# door_board.net
KiCad netlist of a schematic drawn in EAGLE
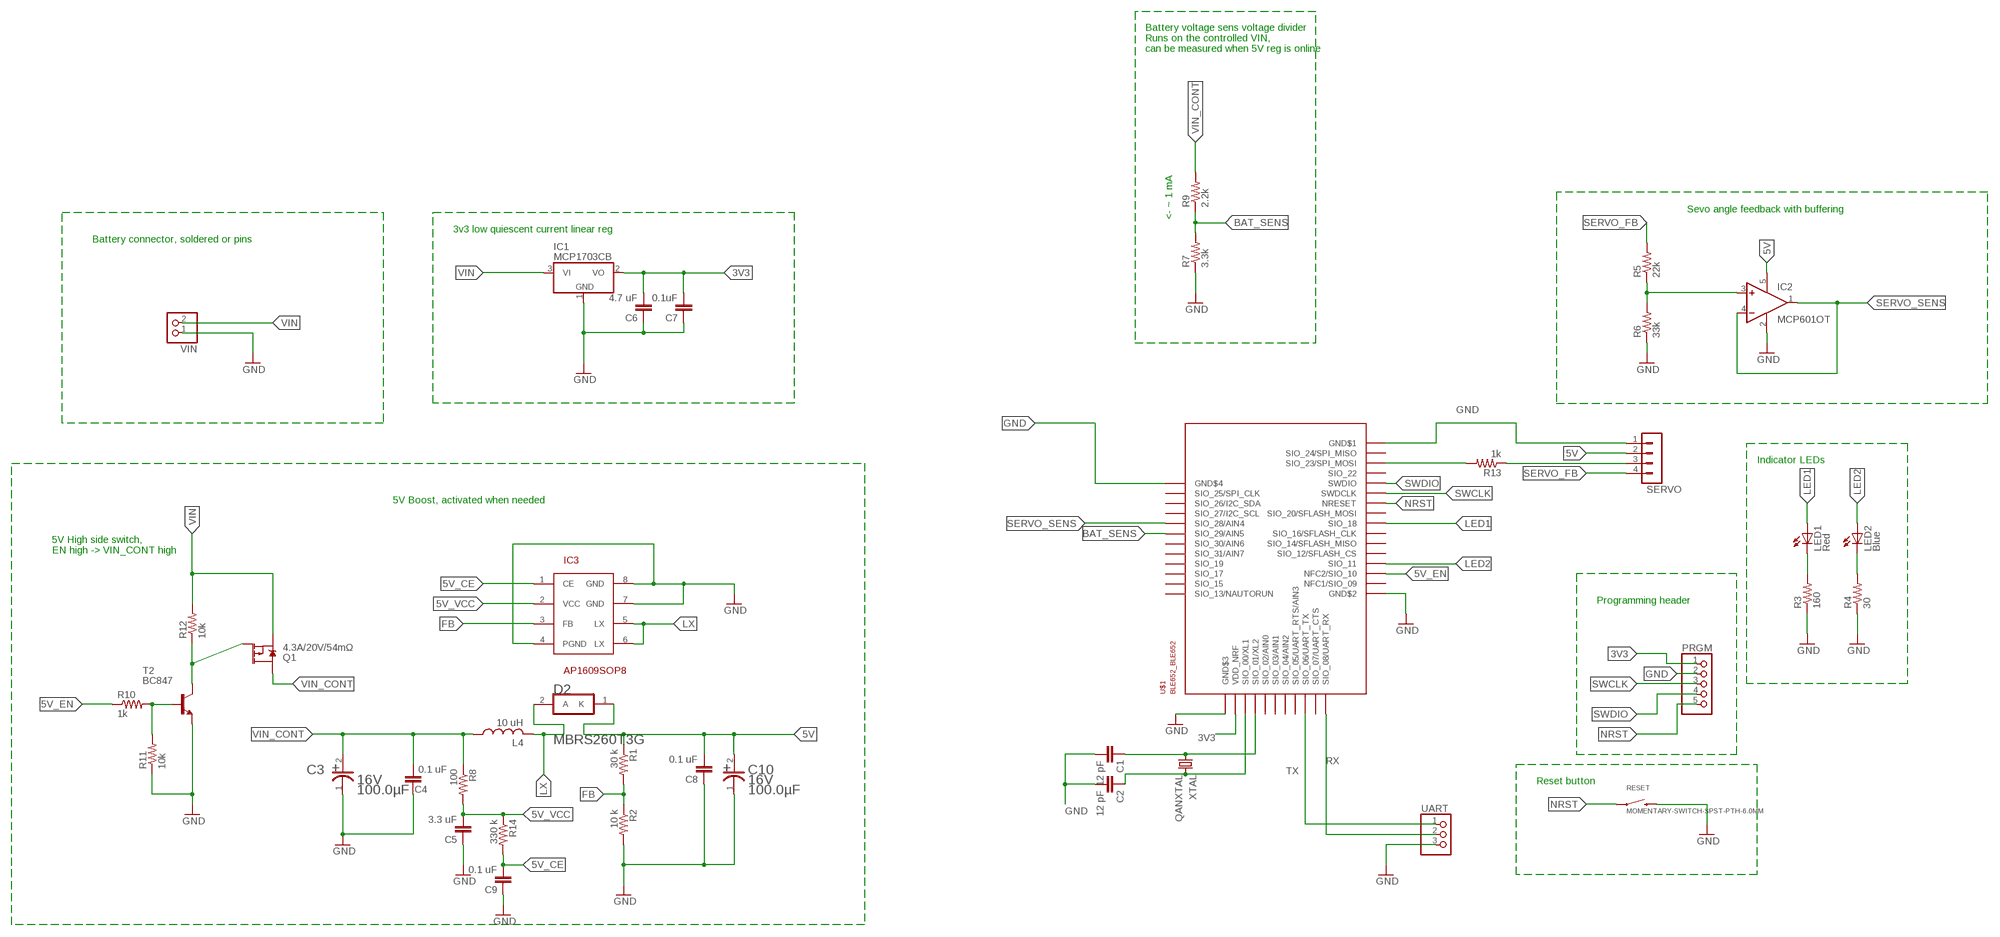
[diagram p0: schematic, sheet 1]

(export (version "E")
  (design (tool "Eeschema 10.0.6"))
  (components
    (comp (ref "C1")
      (value "12 pF")
      (footprint "eagle-import:C0603")
      (libsource (lib "eagle-import") (part "C-EUC0603"))
    )
    (comp (ref "C2")
      (value "12 pF")
      (footprint "eagle-import:C0603")
      (libsource (lib "eagle-import") (part "C-EUC0603"))
    )
    (comp (ref "C3")
      (value "PANASONIC_EEE-FK1C101PPANASONIC_EEE-FK1C101P_0_0")
      (footprint "eagle-import:PANASONIC_EEE-FK1C101P_0")
      (fields
        (field (name "DIGIKEY_PART_NUMBER") "PCE3783CT-ND")
        (field (name "MF") "Panasonic")
        (field (name "MOUSER_PART_NUMBER") "667-EEE-FK1C101P")
      )
      (libsource (lib "eagle-import") (part "PANASONIC_EEE-FK1C101PPANASONIC_EEE-FK1C101P_0_0"))
    )
    (comp (ref "C4")
      (value "0.1 uF")
      (footprint "eagle-import:C0805")
      (libsource (lib "eagle-import") (part "C-EUC0805"))
    )
    (comp (ref "C5")
      (value "3.3 uF")
      (footprint "eagle-import:C0805")
      (libsource (lib "eagle-import") (part "C-EUC0805"))
    )
    (comp (ref "C6")
      (value "4.7 uF")
      (footprint "eagle-import:C0805")
      (libsource (lib "eagle-import") (part "C-EUC0805"))
    )
    (comp (ref "C7")
      (value "0.1uF")
      (footprint "eagle-import:C0805")
      (libsource (lib "eagle-import") (part "C-EUC0805"))
    )
    (comp (ref "C8")
      (value "0.1 uF")
      (footprint "eagle-import:C0805")
      (libsource (lib "eagle-import") (part "C-EUC0805"))
    )
    (comp (ref "C9")
      (value "0.1 uF")
      (footprint "eagle-import:C0805")
      (libsource (lib "eagle-import") (part "C-EUC0805"))
    )
    (comp (ref "C10")
      (value "PANASONIC_EEE-FK1C101PPANASONIC_EEE-FK1C101P_0_0")
      (footprint "eagle-import:PANASONIC_EEE-FK1C101P_0")
      (fields
        (field (name "DIGIKEY_PART_NUMBER") "PCE3783CT-ND")
        (field (name "MF") "Panasonic")
        (field (name "MOUSER_PART_NUMBER") "667-EEE-FK1C101P")
      )
      (libsource (lib "eagle-import") (part "PANASONIC_EEE-FK1C101PPANASONIC_EEE-FK1C101P_0_0"))
    )
    (comp (ref "D2")
      (value "ON_SEMICONDUCTOR_MBRS260T3GON_SEMICONDUCTOR_MBRS260T3G_0_0")
      (footprint "eagle-import:ON_SEMICONDUCTOR_MBRS260T3G_0")
      (fields (field (name "MF") "On Semiconductor") (field (name "MPN") "MBRS260T3G"))
      (libsource (lib "eagle-import") (part "ON_SEMICONDUCTOR_MBRS260T3GON_SEMICONDUCTOR_MBRS260T3G_0_0"))
    )
    (comp (ref "IC1")
      (value "MCP1703CB")
      (footprint "eagle-import:SOT23")
      (libsource (lib "eagle-import") (part "MCP1703CB"))
    )
    (comp (ref "IC2")
      (value "MCP601OT")
      (footprint "eagle-import:SOT23-5")
      (libsource (lib "eagle-import") (part "MCP601OT"))
    )
    (comp (ref "IC3")
      (value "AP1609SOP8")
      (footprint "eagle-import:SOIC127P600X175-8")
      (libsource (lib "eagle-import") (part "AP1609SOP8"))
    )
    (comp (ref "L4")
      (value "10 uH")
      (footprint "eagle-import:SMT")
      (libsource (lib "eagle-import") (part "FDSD0420"))
    )
    (comp (ref "LED1")
      (value "Red")
      (footprint "eagle-import:CHIP-LED0805")
      (libsource (lib "eagle-import") (part "LEDCHIP-LED0805"))
    )
    (comp (ref "LED2")
      (value "Blue")
      (footprint "eagle-import:CHIP-LED0805")
      (libsource (lib "eagle-import") (part "LEDCHIP-LED0805"))
    )
    (comp (ref "PRGM")
      (value "PINHD-1X5")
      (footprint "eagle-import:1X05")
      (libsource (lib "eagle-import") (part "PINHD-1X5"))
    )
    (comp (ref "Q1")
      (value "4.3A/20V/54mΩ")
      (footprint "eagle-import:SOT23-3")
      (libsource (lib "eagle-import") (part "MOSFET_PCH-IRLML2244"))
    )
    (comp (ref "R1")
      (value "30 k")
      (footprint "eagle-import:M0805")
      (libsource (lib "eagle-import") (part "R-US_M0805"))
    )
    (comp (ref "R2")
      (value "10 k")
      (footprint "eagle-import:M0805")
      (libsource (lib "eagle-import") (part "R-US_M0805"))
    )
    (comp (ref "R3")
      (value "160")
      (footprint "eagle-import:M0805")
      (libsource (lib "eagle-import") (part "R-US_M0805"))
    )
    (comp (ref "R4")
      (value "30")
      (footprint "eagle-import:M0805")
      (libsource (lib "eagle-import") (part "R-US_M0805"))
    )
    (comp (ref "R5")
      (value "22k")
      (footprint "eagle-import:M0805")
      (libsource (lib "eagle-import") (part "R-US_M0805"))
    )
    (comp (ref "R6")
      (value "33k")
      (footprint "eagle-import:M0805")
      (libsource (lib "eagle-import") (part "R-US_M0805"))
    )
    (comp (ref "R7")
      (value "3.3k")
      (footprint "eagle-import:M0805")
      (libsource (lib "eagle-import") (part "R-US_M0805"))
    )
    (comp (ref "R8")
      (value "100")
      (footprint "eagle-import:M0805")
      (libsource (lib "eagle-import") (part "R-US_M0805"))
    )
    (comp (ref "R9")
      (value "2.2k")
      (footprint "eagle-import:M0805")
      (libsource (lib "eagle-import") (part "R-US_M0805"))
    )
    (comp (ref "R10")
      (value "1k")
      (footprint "eagle-import:M0805")
      (libsource (lib "eagle-import") (part "R-US_M0805"))
    )
    (comp (ref "R11")
      (value "10k")
      (footprint "eagle-import:M0805")
      (libsource (lib "eagle-import") (part "R-US_M0805"))
    )
    (comp (ref "R12")
      (value "10k")
      (footprint "eagle-import:M0805")
      (libsource (lib "eagle-import") (part "R-US_M0805"))
    )
    (comp (ref "R13")
      (value "1k")
      (footprint "eagle-import:M0805")
      (libsource (lib "eagle-import") (part "R-US_M0805"))
    )
    (comp (ref "R14")
      (value "330 k")
      (footprint "eagle-import:M0805")
      (libsource (lib "eagle-import") (part "R-US_M0805"))
    )
    (comp (ref "RESET")
      (value "MOMENTARY-SWITCH-SPST-PTH-6.0MM")
      (footprint "eagle-import:TACTILE_SWITCH_PTH_6.0MM")
      (libsource (lib "eagle-import") (part "MOMENTARY-SWITCH-SPST-PTH-6.0MM"))
    )
    (comp (ref "SERVO")
      (value "MA04-1")
      (footprint "eagle-import:MA04-1")
      (libsource (lib "eagle-import") (part "MA04-1"))
    )
    (comp (ref "T2")
      (value "BC847")
      (footprint "eagle-import:SOT23")
      (libsource (lib "eagle-import") (part "BC847"))
    )
    (comp (ref "U$1")
      (value "BLE652_BLE652")
      (footprint "eagle-import:BLE652_BL652")
      (libsource (lib "eagle-import") (part "BLE652_BLE652"))
    )
    (comp (ref "UART")
      (value "PINHD-1X3")
      (footprint "eagle-import:1X03")
      (libsource (lib "eagle-import") (part "PINHD-1X3"))
    )
    (comp (ref "VIN")
      (value "PINHD-1X2")
      (footprint "eagle-import:1X02")
      (libsource (lib "eagle-import") (part "PINHD-1X2"))
    )
    (comp (ref "XTAL")
      (value "QANXTAL")
      (footprint "eagle-import:QANTEKXTAL")
      (libsource (lib "eagle-import") (part "QANXTAL"))
    )
  )
  (nets
    (net (code "1") (name "/RX") (class "Default")
      (node (ref "U$1") (pin "P$17") (pinfunction "SIO_08/UART_RX_P$17") (pintype "bidirectional"))
      (node (ref "UART") (pin "2") (pinfunction "2_2") (pintype "passive"))
    )
    (net (code "2") (name "/TX") (class "Default")
      (node (ref "U$1") (pin "P$19") (pinfunction "SIO_06/UART_TX_P$19") (pintype "bidirectional"))
      (node (ref "UART") (pin "1") (pinfunction "1_1") (pintype "passive"))
    )
    (net (code "3") (name "3V3") (class "Default")
      (node (ref "C6") (pin "2") (pinfunction "2_2") (pintype "passive"))
      (node (ref "C7") (pin "2") (pinfunction "2_2") (pintype "passive"))
      (node (ref "IC1") (pin "2") (pinfunction "VO_2") (pintype "passive"))
      (node (ref "PRGM") (pin "1") (pinfunction "1_1") (pintype "passive"))
      (node (ref "U$1") (pin "P$26") (pinfunction "VDD_NRF_P$26") (pintype "power_in"))
    )
    (net (code "4") (name "5V") (class "Default")
      (node (ref "C10") (pin "2") (pinfunction "ANODE_2") (pintype "bidirectional"))
      (node (ref "C8") (pin "2") (pinfunction "2_2") (pintype "passive"))
      (node (ref "D2") (pin "1") (pinfunction "K_1") (pintype "passive"))
      (node (ref "IC2") (pin "5") (pinfunction "V+_5") (pintype "power_in"))
      (node (ref "R1") (pin "1") (pinfunction "1_1") (pintype "passive"))
      (node (ref "SERVO") (pin "2") (pinfunction "2_2") (pintype "passive"))
    )
    (net (code "5") (name "5V_CE") (class "Default")
      (node (ref "C9") (pin "2") (pinfunction "2_2") (pintype "passive"))
      (node (ref "IC3") (pin "1") (pinfunction "CE_1") (pintype "input"))
      (node (ref "R14") (pin "2") (pinfunction "2_2") (pintype "passive"))
    )
    (net (code "6") (name "5V_EN") (class "Default")
      (node (ref "R10") (pin "1") (pinfunction "1_1") (pintype "passive"))
      (node (ref "U$1") (pin "P$14") (pinfunction "NFC2/SIO_10_P$14") (pintype "bidirectional"))
    )
    (net (code "7") (name "5V_VCC") (class "Default")
      (node (ref "C5") (pin "2") (pinfunction "2_2") (pintype "passive"))
      (node (ref "IC3") (pin "2") (pinfunction "VCC_2") (pintype "power_in"))
      (node (ref "R14") (pin "1") (pinfunction "1_1") (pintype "passive"))
      (node (ref "R8") (pin "2") (pinfunction "2_2") (pintype "passive"))
    )
    (net (code "8") (name "BAT_SENS") (class "Default")
      (node (ref "R7") (pin "2") (pinfunction "2_2") (pintype "passive"))
      (node (ref "R9") (pin "1") (pinfunction "1_1") (pintype "passive"))
      (node (ref "U$1") (pin "P$34") (pinfunction "SIO_29/AIN5_P$34") (pintype "bidirectional"))
    )
    (net (code "9") (name "FB") (class "Default")
      (node (ref "IC3") (pin "3") (pinfunction "FB_3") (pintype "bidirectional"))
      (node (ref "R1") (pin "2") (pinfunction "2_2") (pintype "passive"))
      (node (ref "R2") (pin "1") (pinfunction "1_1") (pintype "passive"))
    )
    (net (code "10") (name "GND") (class "Default")
      (node (ref "C1") (pin "2") (pinfunction "2_2") (pintype "passive"))
      (node (ref "C10") (pin "1") (pinfunction "CATHODE_1") (pintype "bidirectional"))
      (node (ref "C2") (pin "2") (pinfunction "2_2") (pintype "passive"))
      (node (ref "C3") (pin "1") (pinfunction "CATHODE_1") (pintype "bidirectional"))
      (node (ref "C4") (pin "1") (pinfunction "1_1") (pintype "passive"))
      (node (ref "C5") (pin "1") (pinfunction "1_1") (pintype "passive"))
      (node (ref "C6") (pin "1") (pinfunction "1_1") (pintype "passive"))
      (node (ref "C7") (pin "1") (pinfunction "1_1") (pintype "passive"))
      (node (ref "C8") (pin "1") (pinfunction "1_1") (pintype "passive"))
      (node (ref "C9") (pin "1") (pinfunction "1_1") (pintype "passive"))
      (node (ref "IC1") (pin "1") (pinfunction "GND_1") (pintype "passive"))
      (node (ref "IC2") (pin "2") (pinfunction "V-_2") (pintype "power_in"))
      (node (ref "IC3") (pin "4") (pinfunction "PGND_4") (pintype "power_in"))
      (node (ref "IC3") (pin "7") (pinfunction "GND_7") (pintype "power_in"))
      (node (ref "IC3") (pin "8") (pinfunction "GND_8") (pintype "power_in"))
      (node (ref "PRGM") (pin "2") (pinfunction "2_2") (pintype "passive"))
      (node (ref "R11") (pin "1") (pinfunction "1_1") (pintype "passive"))
      (node (ref "R2") (pin "2") (pinfunction "2_2") (pintype "passive"))
      (node (ref "R3") (pin "1") (pinfunction "1_1") (pintype "passive"))
      (node (ref "R4") (pin "1") (pinfunction "1_1") (pintype "passive"))
      (node (ref "R6") (pin "1") (pinfunction "1_1") (pintype "passive"))
      (node (ref "R7") (pin "1") (pinfunction "1_1") (pintype "passive"))
      (node (ref "RESET") (pin "3") (pinfunction "2_3") (pintype "passive"))
      (node (ref "SERVO") (pin "1") (pinfunction "1_1") (pintype "passive"))
      (node (ref "T2") (pin "2") (pinfunction "E_2") (pintype "passive"))
      (node (ref "U$1") (pin "P$1") (pinfunction "GND$1_P$1") (pintype "power_in"))
      (node (ref "U$1") (pin "P$16") (pinfunction "GND$2_P$16") (pintype "power_in"))
      (node (ref "U$1") (pin "P$27") (pinfunction "GND$3_P$27") (pintype "power_in"))
      (node (ref "U$1") (pin "P$39") (pinfunction "GND$4_P$39") (pintype "power_in"))
      (node (ref "UART") (pin "3") (pinfunction "3_3") (pintype "passive"))
      (node (ref "VIN") (pin "1") (pinfunction "1_1") (pintype "passive"))
    )
    (net (code "11") (name "LED1") (class "Default")
      (node (ref "LED1") (pin "A") (pinfunction "A_A") (pintype "passive"))
      (node (ref "U$1") (pin "P$9") (pinfunction "SIO_18_P$9") (pintype "bidirectional"))
    )
    (net (code "12") (name "LED2") (class "Default")
      (node (ref "LED2") (pin "A") (pinfunction "A_A") (pintype "passive"))
      (node (ref "U$1") (pin "P$13") (pinfunction "SIO_11_P$13") (pintype "bidirectional"))
    )
    (net (code "13") (name "LX") (class "Default")
      (node (ref "D2") (pin "2") (pinfunction "A_2") (pintype "passive"))
      (node (ref "IC3") (pin "5") (pinfunction "LX_5") (pintype "bidirectional"))
      (node (ref "IC3") (pin "6") (pinfunction "LX_6") (pintype "bidirectional"))
      (node (ref "L4") (pin "P2") (pinfunction "2_P2") (pintype "passive"))
    )
    (net (code "14") (name "NRST") (class "Default")
      (node (ref "PRGM") (pin "5") (pinfunction "5_5") (pintype "passive"))
      (node (ref "RESET") (pin "1") (pinfunction "1_1") (pintype "passive"))
      (node (ref "U$1") (pin "P$7") (pinfunction "NRESET_P$7") (pintype "bidirectional"))
    )
    (net (code "15") (name "Net-(IC2-+IN)") (class "Default")
      (node (ref "IC2") (pin "3") (pinfunction "+IN_3") (pintype "input"))
      (node (ref "R5") (pin "1") (pinfunction "1_1") (pintype "passive"))
      (node (ref "R6") (pin "2") (pinfunction "2_2") (pintype "passive"))
    )
    (net (code "16") (name "Net-(LED1-PadC)") (class "Default")
      (node (ref "LED1") (pin "C") (pinfunction "C_C") (pintype "passive"))
      (node (ref "R3") (pin "2") (pinfunction "2_2") (pintype "passive"))
    )
    (net (code "17") (name "Net-(LED2-PadC)") (class "Default")
      (node (ref "LED2") (pin "C") (pinfunction "C_C") (pintype "passive"))
      (node (ref "R4") (pin "2") (pinfunction "2_2") (pintype "passive"))
    )
    (net (code "18") (name "Net-(Q1-G)") (class "Default")
      (node (ref "Q1") (pin "1") (pinfunction "G_1") (pintype "bidirectional"))
      (node (ref "R12") (pin "1") (pinfunction "1_1") (pintype "passive"))
      (node (ref "T2") (pin "3") (pinfunction "C_3") (pintype "passive"))
    )
    (net (code "19") (name "Net-(R13-Pad1)") (class "Default")
      (node (ref "R13") (pin "1") (pinfunction "1_1") (pintype "passive"))
      (node (ref "SERVO") (pin "3") (pinfunction "3_3") (pintype "passive"))
    )
    (net (code "20") (name "Net-(T2-B)") (class "Default")
      (node (ref "R10") (pin "2") (pinfunction "2_2") (pintype "passive"))
      (node (ref "R11") (pin "2") (pinfunction "2_2") (pintype "passive"))
      (node (ref "T2") (pin "1") (pinfunction "B_1") (pintype "passive"))
    )
    (net (code "21") (name "Net-(U$1-SIO_00{slash}XL1)") (class "Default")
      (node (ref "C2") (pin "1") (pinfunction "1_1") (pintype "passive"))
      (node (ref "U$1") (pin "P$25") (pinfunction "SIO_00/XL1_P$25") (pintype "bidirectional"))
      (node (ref "XTAL") (pin "2") (pinfunction "2_2") (pintype "passive"))
    )
    (net (code "22") (name "Net-(U$1-SIO_01{slash}XL2)") (class "Default")
      (node (ref "C1") (pin "1") (pinfunction "1_1") (pintype "passive"))
      (node (ref "U$1") (pin "P$24") (pinfunction "SIO_01/XL2_P$24") (pintype "bidirectional"))
      (node (ref "XTAL") (pin "1") (pinfunction "1_1") (pintype "passive"))
    )
    (net (code "23") (name "Net-(U$1-SIO_23{slash}SPI_MOSI)") (class "Default")
      (node (ref "R13") (pin "2") (pinfunction "2_2") (pintype "passive"))
      (node (ref "U$1") (pin "P$3") (pinfunction "SIO_23/SPI_MOSI_P$3") (pintype "bidirectional"))
    )
    (net (code "24") (name "SERVO_FB") (class "Default")
      (node (ref "R5") (pin "2") (pinfunction "2_2") (pintype "passive"))
      (node (ref "SERVO") (pin "4") (pinfunction "4_4") (pintype "passive"))
    )
    (net (code "25") (name "SERVO_SENS") (class "Default")
      (node (ref "IC2") (pin "1") (pinfunction "OUT_1") (pintype "output"))
      (node (ref "IC2") (pin "4") (pinfunction "-IN_4") (pintype "input"))
      (node (ref "U$1") (pin "P$35") (pinfunction "SIO_28/AIN4_P$35") (pintype "bidirectional"))
    )
    (net (code "26") (name "SWCLK") (class "Default")
      (node (ref "PRGM") (pin "3") (pinfunction "3_3") (pintype "passive"))
      (node (ref "U$1") (pin "P$6") (pinfunction "SWDCLK_P$6") (pintype "input"))
    )
    (net (code "27") (name "SWDIO") (class "Default")
      (node (ref "PRGM") (pin "4") (pinfunction "4_4") (pintype "passive"))
      (node (ref "U$1") (pin "P$5") (pinfunction "SWDIO_P$5") (pintype "bidirectional"))
    )
    (net (code "28") (name "VIN") (class "Default")
      (node (ref "IC1") (pin "3") (pinfunction "VI_3") (pintype "input"))
      (node (ref "Q1") (pin "2") (pinfunction "S_2") (pintype "bidirectional"))
      (node (ref "R12") (pin "2") (pinfunction "2_2") (pintype "passive"))
      (node (ref "VIN") (pin "2") (pinfunction "2_2") (pintype "passive"))
    )
    (net (code "29") (name "VIN_CONT") (class "Default")
      (node (ref "C3") (pin "2") (pinfunction "ANODE_2") (pintype "bidirectional"))
      (node (ref "C4") (pin "2") (pinfunction "2_2") (pintype "passive"))
      (node (ref "L4") (pin "P1") (pinfunction "1_P1") (pintype "passive"))
      (node (ref "Q1") (pin "3") (pinfunction "D_3") (pintype "bidirectional"))
      (node (ref "R8") (pin "1") (pinfunction "1_1") (pintype "passive"))
      (node (ref "R9") (pin "2") (pinfunction "2_2") (pintype "passive"))
    )
    (net (code "30") (name "unconnected-(U$1-NFC1{slash}SIO_09-PadP$15)") (class "Default")
      (node (ref "U$1") (pin "P$15") (pinfunction "NFC1/SIO_09_P$15") (pintype "bidirectional"))
    )
    (net (code "31") (name "unconnected-(U$1-SIO_02{slash}AIN0-PadP$23)") (class "Default")
      (node (ref "U$1") (pin "P$23") (pinfunction "SIO_02/AIN0_P$23") (pintype "bidirectional"))
    )
    (net (code "32") (name "unconnected-(U$1-SIO_03{slash}AIN1-PadP$22)") (class "Default")
      (node (ref "U$1") (pin "P$22") (pinfunction "SIO_03/AIN1_P$22") (pintype "bidirectional"))
    )
    (net (code "33") (name "unconnected-(U$1-SIO_04{slash}AIN2-PadP$21)") (class "Default")
      (node (ref "U$1") (pin "P$21") (pinfunction "SIO_04/AIN2_P$21") (pintype "bidirectional"))
    )
    (net (code "34") (name "unconnected-(U$1-SIO_05{slash}UART_RTS{slash}AIN3-PadP$20)") (class "Default")
      (node (ref "U$1") (pin "P$20") (pinfunction "SIO_05/UART_RTS/AIN3_P$20") (pintype "bidirectional"))
    )
    (net (code "35") (name "unconnected-(U$1-SIO_07{slash}UART_CTS-PadP$18)") (class "Default")
      (node (ref "U$1") (pin "P$18") (pinfunction "SIO_07/UART_CTS_P$18") (pintype "bidirectional"))
    )
    (net (code "36") (name "unconnected-(U$1-SIO_12{slash}SFLASH_CS-PadP$12)") (class "Default")
      (node (ref "U$1") (pin "P$12") (pinfunction "SIO_12/SFLASH_CS_P$12") (pintype "bidirectional"))
    )
    (net (code "37") (name "unconnected-(U$1-SIO_13{slash}NAUTORUN-PadP$28)") (class "Default")
      (node (ref "U$1") (pin "P$28") (pinfunction "SIO_13/NAUTORUN_P$28") (pintype "bidirectional"))
    )
    (net (code "38") (name "unconnected-(U$1-SIO_14{slash}SFLASH_MISO-PadP$11)") (class "Default")
      (node (ref "U$1") (pin "P$11") (pinfunction "SIO_14/SFLASH_MISO_P$11") (pintype "bidirectional"))
    )
    (net (code "39") (name "unconnected-(U$1-SIO_15-PadP$29)") (class "Default")
      (node (ref "U$1") (pin "P$29") (pinfunction "SIO_15_P$29") (pintype "bidirectional"))
    )
    (net (code "40") (name "unconnected-(U$1-SIO_16{slash}SFLASH_CLK-PadP$10)") (class "Default")
      (node (ref "U$1") (pin "P$10") (pinfunction "SIO_16/SFLASH_CLK_P$10") (pintype "bidirectional"))
    )
    (net (code "41") (name "unconnected-(U$1-SIO_17-PadP$30)") (class "Default")
      (node (ref "U$1") (pin "P$30") (pinfunction "SIO_17_P$30") (pintype "bidirectional"))
    )
    (net (code "42") (name "unconnected-(U$1-SIO_19-PadP$31)") (class "Default")
      (node (ref "U$1") (pin "P$31") (pinfunction "SIO_19_P$31") (pintype "bidirectional"))
    )
    (net (code "43") (name "unconnected-(U$1-SIO_20{slash}SFLASH_MOSI-PadP$8)") (class "Default")
      (node (ref "U$1") (pin "P$8") (pinfunction "SIO_20/SFLASH_MOSI_P$8") (pintype "bidirectional"))
    )
    (net (code "44") (name "unconnected-(U$1-SIO_22-PadP$4)") (class "Default")
      (node (ref "U$1") (pin "P$4") (pinfunction "SIO_22_P$4") (pintype "bidirectional"))
    )
    (net (code "45") (name "unconnected-(U$1-SIO_24{slash}SPI_MISO-PadP$2)") (class "Default")
      (node (ref "U$1") (pin "P$2") (pinfunction "SIO_24/SPI_MISO_P$2") (pintype "bidirectional"))
    )
    (net (code "46") (name "unconnected-(U$1-SIO_25{slash}SPI_CLK-PadP$38)") (class "Default")
      (node (ref "U$1") (pin "P$38") (pinfunction "SIO_25/SPI_CLK_P$38") (pintype "bidirectional"))
    )
    (net (code "47") (name "unconnected-(U$1-SIO_26{slash}I2C_SDA-PadP$37)") (class "Default")
      (node (ref "U$1") (pin "P$37") (pinfunction "SIO_26/I2C_SDA_P$37") (pintype "bidirectional"))
    )
    (net (code "48") (name "unconnected-(U$1-SIO_27{slash}I2C_SCL-PadP$36)") (class "Default")
      (node (ref "U$1") (pin "P$36") (pinfunction "SIO_27/I2C_SCL_P$36") (pintype "bidirectional"))
    )
    (net (code "49") (name "unconnected-(U$1-SIO_30{slash}AIN6-PadP$33)") (class "Default")
      (node (ref "U$1") (pin "P$33") (pinfunction "SIO_30/AIN6_P$33") (pintype "bidirectional"))
    )
    (net (code "50") (name "unconnected-(U$1-SIO_31{slash}AIN7-PadP$32)") (class "Default")
      (node (ref "U$1") (pin "P$32") (pinfunction "SIO_31/AIN7_P$32") (pintype "bidirectional"))
    )
  )
)
